# main.net
KiCad netlist of a schematic drawn in Altium Designer
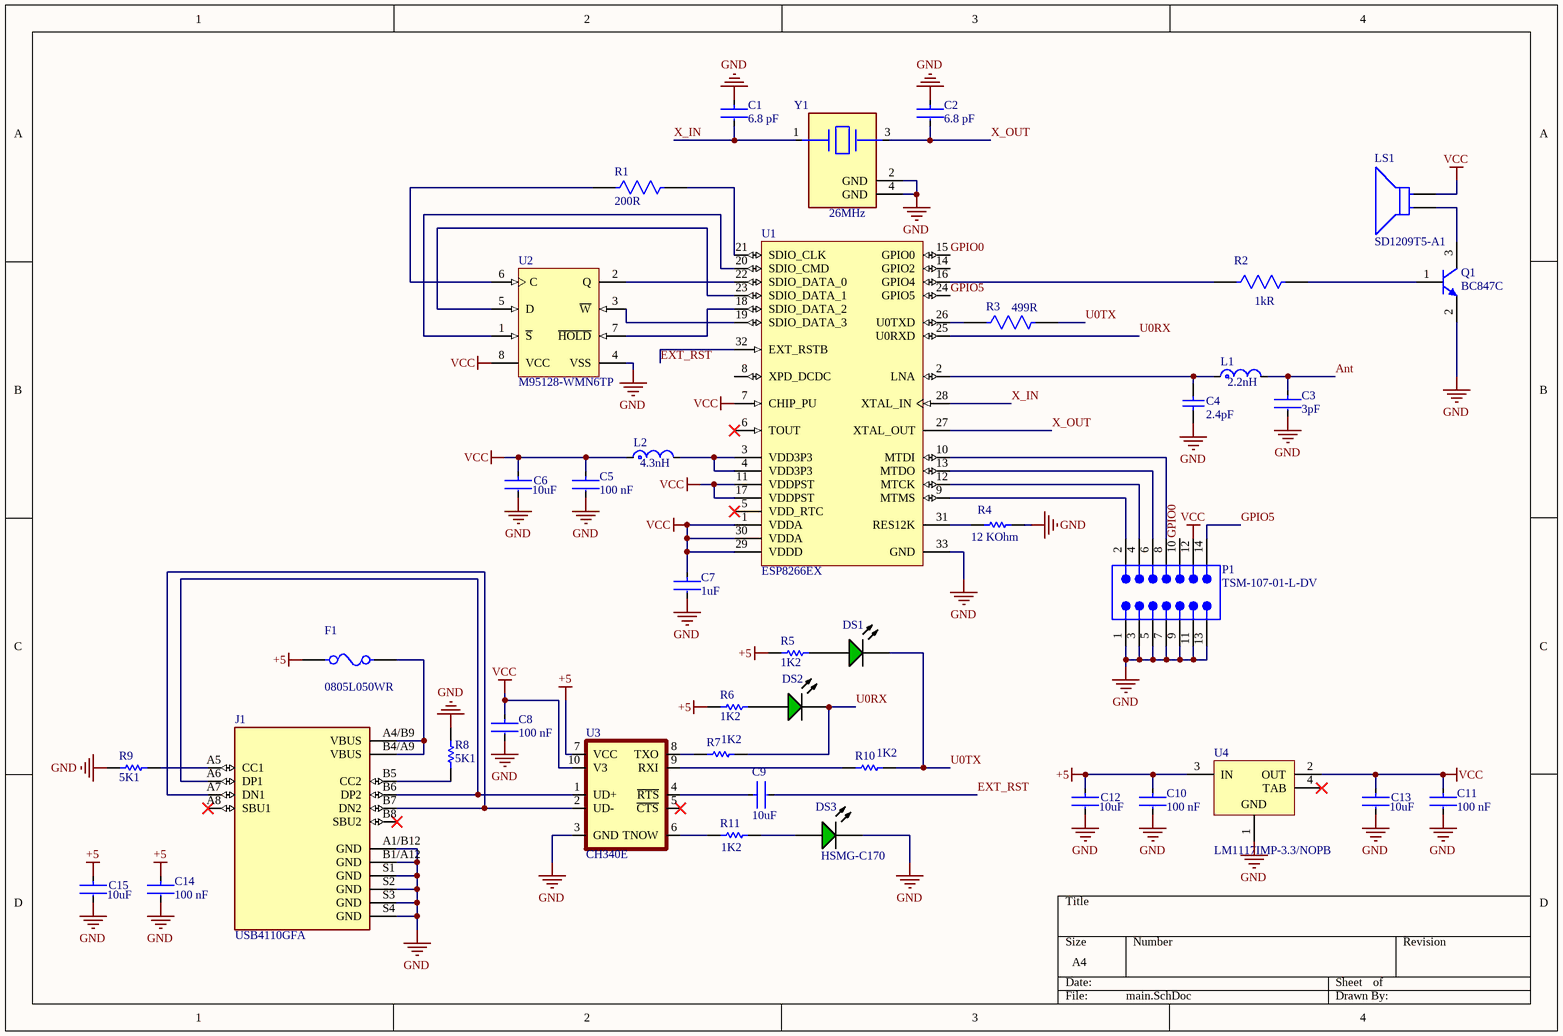
[diagram p0: main.SchDoc]

(export (version "E")
  (design (tool "Eeschema 10.0.6"))
  (components
    (comp (ref "C1")
      (value "C0402C689C5GACTU")
      (footprint "FP-C0402-BB-MFG")
      (description "CAP CER 6.8PF 50V NP0 0402")
      (fields
        (field (name "OCTOPART") "https://octopart.com/c0402c689c5gactu-kemet-9143567")
        (field (name "MANUFACTURER") "Kemet")
        (field (name "CAPACITANCE") "6.8 pF")
      )
      (libsource (lib "Altium Content Vault") (part "b4654b650e69147ec39a6b967a45e02"))
    )
    (comp (ref "C2")
      (value "C0402C689C5GACTU")
      (footprint "FP-C0402-BB-MFG")
      (description "CAP CER 6.8PF 50V NP0 0402")
      (fields
        (field (name "OCTOPART") "https://octopart.com/c0402c689c5gactu-kemet-9143567")
        (field (name "MANUFACTURER") "Kemet")
        (field (name "CAPACITANCE") "6.8 pF")
      )
      (libsource (lib "Altium Content Vault") (part "b4654b650e69147ec39a6b967a45e02"))
    )
    (comp (ref "C3")
      (value "GJM1555C1H3R0BB01D")
      (footprint "FP-GJM155-0_05-IPC_C")
      (description "Multi-Layer Ceramic Capacitor 3pF C0G  ±0.1pF 0402 Paper T/R")
      (fields (field (name "CAPACITANCE") "3pF") (field (name "VOLTAGE") "50V"))
      (libsource (lib "Altium Content Vault") (part "02cd4be3c70576c341d710602a673aa"))
    )
    (comp (ref "C4")
      (value "2.4pF")
      (footprint "CAPC1006X50X20ML10T10")
      (fields
        (field (name "PART NUMBER") "04023J2R4BBSTR")
        (field (name "MANUFACTURER") "AVX Interconnect / Elco")
      )
      (libsource (lib "Altium Content Vault") (part "CAP"))
    )
    (comp (ref "C5")
      (value "100 nF")
      (footprint "FP-CC0402-MFG")
      (description "CAP CER 0.1UF 50V X7R 0402")
      (fields
        (field (name "MANUFACTURER") "YAGEO")
        (field (name "OCTOPART") "https://octopart.com/cc0402krx7r9bb104-yageo-56536067")
      )
      (libsource (lib "Altium Content Vault") (part "11868f565c42a9108669ba33697ecf6"))
    )
    (comp (ref "C6")
      (value "C1608X5R1A106K080AC")
      (footprint "FP-C1608-080-0_1-MFG")
      (description "Multilayer Ceramic Capacitors 10μF ±10% 10V X5R SMD 0603")
      (fields
        (field (name "VOLTAGE") "10V")
        (field (name "TOLERANCE") "10%")
        (field (name "CAPACITANCE") "10uF")
      )
      (libsource (lib "Altium Content Vault") (part "236180d848d6139a670b325ea6854c9"))
    )
    (comp (ref "C7")
      (value "1uF")
      (footprint "FP-GRM15-0_1-MFG")
      (description "CAP CER 1UF 10V X5R 0402")
      (fields
        (field (name "OCTOPART") "https://octopart.com/grm155r61a105ke15d-murata-197442")
        (field (name "MANUFACTURER PART NUMBER") "GRM155R61A105KE15D")
      )
      (libsource (lib "Altium Content Vault") (part "02cd4be3c70576c341d710602a673aa"))
    )
    (comp (ref "C8")
      (value "100 nF")
      (footprint "FP-CC0402-MFG")
      (description "CAP CER 0.1UF 50V X7R 0402")
      (fields
        (field (name "MANUFACTURER") "YAGEO")
        (field (name "OCTOPART") "https://octopart.com/cc0402krx7r9bb104-yageo-56536067")
      )
      (libsource (lib "Altium Content Vault") (part "11868f565c42a9108669ba33697ecf6"))
    )
    (comp (ref "C9")
      (value "C1608X5R1A106K080AC")
      (footprint "FP-C1608-080-0_1-MFG")
      (description "Multilayer Ceramic Capacitors 10μF ±10% 10V X5R SMD 0603")
      (fields
        (field (name "VOLTAGE") "10V")
        (field (name "TOLERANCE") "10%")
        (field (name "CAPACITANCE") "10uF")
      )
      (libsource (lib "Altium Content Vault") (part "236180d848d6139a670b325ea6854c9"))
    )
    (comp (ref "C10")
      (value "100 nF")
      (footprint "FP-CC0402-MFG")
      (description "CAP CER 0.1UF 50V X7R 0402")
      (fields
        (field (name "MANUFACTURER") "YAGEO")
        (field (name "OCTOPART") "https://octopart.com/cc0402krx7r9bb104-yageo-56536067")
      )
      (libsource (lib "Altium Content Vault") (part "11868f565c42a9108669ba33697ecf6"))
    )
    (comp (ref "C11")
      (value "100 nF")
      (footprint "FP-CC0402-MFG")
      (description "CAP CER 0.1UF 50V X7R 0402")
      (fields
        (field (name "MANUFACTURER") "YAGEO")
        (field (name "OCTOPART") "https://octopart.com/cc0402krx7r9bb104-yageo-56536067")
      )
      (libsource (lib "Altium Content Vault") (part "11868f565c42a9108669ba33697ecf6"))
    )
    (comp (ref "C12")
      (value "C1608X5R1A106K080AC")
      (footprint "FP-C1608-080-0_1-MFG")
      (description "Multilayer Ceramic Capacitors 10μF ±10% 10V X5R SMD 0603")
      (fields
        (field (name "VOLTAGE") "10V")
        (field (name "TOLERANCE") "10%")
        (field (name "CAPACITANCE") "10uF")
      )
      (libsource (lib "Altium Content Vault") (part "236180d848d6139a670b325ea6854c9"))
    )
    (comp (ref "C13")
      (value "C1608X5R1A106K080AC")
      (footprint "FP-C1608-080-0_1-MFG")
      (description "Multilayer Ceramic Capacitors 10μF ±10% 10V X5R SMD 0603")
      (fields
        (field (name "VOLTAGE") "10V")
        (field (name "TOLERANCE") "10%")
        (field (name "CAPACITANCE") "10uF")
      )
      (libsource (lib "Altium Content Vault") (part "236180d848d6139a670b325ea6854c9"))
    )
    (comp (ref "C14")
      (value "100 nF")
      (footprint "FP-CC0402-MFG")
      (description "CAP CER 0.1UF 50V X7R 0402")
      (fields
        (field (name "MANUFACTURER") "YAGEO")
        (field (name "OCTOPART") "https://octopart.com/cc0402krx7r9bb104-yageo-56536067")
      )
      (libsource (lib "Altium Content Vault") (part "11868f565c42a9108669ba33697ecf6"))
    )
    (comp (ref "C15")
      (value "C1608X5R1A106K080AC")
      (footprint "FP-C1608-080-0_1-MFG")
      (description "Multilayer Ceramic Capacitors 10μF ±10% 10V X5R SMD 0603")
      (fields
        (field (name "VOLTAGE") "10V")
        (field (name "TOLERANCE") "10%")
        (field (name "CAPACITANCE") "10uF")
      )
      (libsource (lib "Altium Content Vault") (part "236180d848d6139a670b325ea6854c9"))
    )
    (comp (ref "DS1")
      (value "HSMG-C170")
      (footprint "AVAG-HSMX-C170_V")
      (description "Chip LED, Green, 2.2 V, -40 to 85 degC, 2-Pin SMD, Pb-Free, Tape and Reel")
      (fields (field (name "MANUFACTURER") "Avago"))
      (libsource (lib "Altium Content Vault") (part "LED_GREEN_A1K2-2"))
    )
    (comp (ref "DS2")
      (value "HSMG-C170")
      (footprint "AVAG-HSMX-C170_V")
      (description "Chip LED, Green, 2.2 V, -40 to 85 degC, 2-Pin SMD, Pb-Free, Tape and Reel")
      (fields (field (name "MANUFACTURER") "Avago"))
      (libsource (lib "Altium Content Vault") (part "LED_GREEN_A1K2-2"))
    )
    (comp (ref "DS3")
      (value "HSMG-C170")
      (footprint "AVAG-HSMX-C170_V")
      (description "Chip LED, Green, 2.2 V, -40 to 85 degC, 2-Pin SMD, Pb-Free, Tape and Reel")
      (fields (field (name "MANUFACTURER") "Avago"))
      (libsource (lib "Altium Content Vault") (part "LED_GREEN_A1K2-2"))
    )
    (comp (ref "F1")
      (value "0805L050WR")
      (footprint "FP-0805L-MFG")
      (description "PTC RESET FUSE 6V 500MA 0805")
      (fields
        (field (name "MANUFACTURER") "Littelfuse Inc.")
        (field (name "OCTOPART") "https://octopart.com/0805l050wr-littelfuse-673858")
      )
      (libsource (lib "Altium Content Vault") (part "5bcf9b9f640e542cf0359d10258e979"))
    )
    (comp (ref "J1")
      (value "USB4110GFA")
      (footprint "GCT_USB4110GFA")
      (fields (field (name "MF") "Global Connector Technology"))
      (libsource (lib "USB4110GFA") (part "USB4110GFA"))
    )
    (comp (ref "L1")
      (value "LQG15HN2N2S02D")
      (footprint "FP-LQG15HH_02-IPC_C")
      (description "Multilayer type RF Inductor 2.2nH ±0.3nH 0.09Ω 900mA 0402")
      (fields (field (name "INDUCTANCE") "2.2nH"))
      (libsource (lib "Altium Content Vault") (part "4cc4b267dca4c8e51f7102f422741d8"))
    )
    (comp (ref "L2")
      (value "LQG15HN4N3S02D")
      (footprint "FP-LQG15HH_02-MFG")
      (description "Multilayer type RF Inductor 4.3nH ±0.3nH 0.15Ω 700mA 0402")
      (fields (field (name "INDUCTANCE") "4.3nH"))
      (libsource (lib "Altium Content Vault") (part "4cc4b267dca4c8e51f7102f422741d8"))
    )
    (comp (ref "LS1")
      (value "SD1209T5-A1")
      (footprint "FP-SD1209-MFG")
      (description "AUDIO MAGNETIC XDCR 3-6V TH")
      (libsource (lib "Altium Content Vault") (part "1973c4b650225fd2ddacaff6b763965"))
    )
    (comp (ref "P1")
      (value "TSM-107-01-L-DV")
      (footprint "SMTC-TSM-107-01-X-DV")
      (fields (field (name "MANUFACTURER") "Samtec"))
      (libsource (lib "Altium Content Vault") (part "SMTC-TSM-107-01-X-X"))
    )
    (comp (ref "Q1")
      (value "BC847C")
      (footprint "INF-SOT23_L")
      (description "NPN Silicon AF Transistor, 45 V VCEO, 100 mA IC, SOT23, Reel, Green")
      (fields (field (name "MANUFACTURER") "Infineon"))
      (libsource (lib "Altium Content Vault") (part "INF-BJTNPN-BEC-3"))
    )
    (comp (ref "R1")
      (value "CRCW0402200RFKED")
      (footprint "FP-CRCW0402-e3-IPC_C")
      (description "RES Thick Film, 200Ω, 1%, 0.063W, 100ppm/°C, 0402")
      (fields (field (name "RESISTANCE") "200R") (field (name "TOLERANCE") "1%"))
      (libsource (lib "Altium Content Vault") (part "1029c3af85768c4190bb7ad29bc67b5"))
    )
    (comp (ref "R2")
      (value "ERA-3AEB102V")
      (footprint "FP-ERA3A-IPC_C")
      (description "RES SMD 1K OHM 0.1% 1/10W 0603")
      (fields (field (name "TOLERANCE") "0.1%") (field (name "RESISTANCE") "1kR"))
      (libsource (lib "Altium Content Vault") (part "1029c3af85768c4190bb7ad29bc67b5"))
    )
    (comp (ref "R3")
      (value "RC0402FR-07499RL")
      (footprint "FP-RC0402-0_4-IPC_A")
      (description "RES 499 OHM 1% 1/16W 0402")
      (fields (field (name "RESISTANCE") "499R") (field (name "TOLERANCE") "1%"))
      (libsource (lib "Altium Content Vault") (part "1029c3af85768c4190bb7ad29bc67b5"))
    )
    (comp (ref "R4")
      (value "ERJ-2RKF1202X")
      (footprint "RESC1005X40X25ML05T05")
      (description "Chip Resistor, 12 KOhm, +/- 1%, 0.1 W, -55 to 155 degC, 0402 (1005 Metric), RoHS, Tape and Reel")
      (fields (field (name "RESISTANCE") "12 KOhm") (field (name "TOLERANCE") "1%"))
      (libsource (lib "Altium Content Vault") (part "RES-2"))
    )
    (comp (ref "R5")
      (value "1K2")
      (footprint "RESC1005X40X25NL05T05")
      (fields (field (name "PART NUMBER") "CRCW04021K20FKED") (field (name "MANUFACTURER") "Vishay Dale"))
      (libsource (lib "Altium Content Vault") (part "RES"))
    )
    (comp (ref "R6")
      (value "1K2")
      (footprint "RESC1005X40X25NL05T05")
      (fields (field (name "PART NUMBER") "CRCW04021K20FKED") (field (name "MANUFACTURER") "Vishay Dale"))
      (libsource (lib "Altium Content Vault") (part "RES"))
    )
    (comp (ref "R7")
      (value "1K2")
      (footprint "RESC1005X40X25NL05T05")
      (fields (field (name "PART NUMBER") "CRCW04021K20FKED") (field (name "MANUFACTURER") "Vishay Dale"))
      (libsource (lib "Altium Content Vault") (part "RES"))
    )
    (comp (ref "R8")
      (value "5K1")
      (footprint "RESC1608X55X25ML10T15")
      (fields (field (name "MANUFACTURER") "Yageo") (field (name "PART NUMBER") "RC0603FR-075K1L"))
      (libsource (lib "Altium Content Vault") (part "RES"))
    )
    (comp (ref "R9")
      (value "5K1")
      (footprint "RESC1608X55X25ML10T15")
      (fields (field (name "MANUFACTURER") "Yageo") (field (name "PART NUMBER") "RC0603FR-075K1L"))
      (libsource (lib "Altium Content Vault") (part "RES"))
    )
    (comp (ref "R10")
      (value "1K2")
      (footprint "RESC1005X40X25NL05T05")
      (fields (field (name "PART NUMBER") "CRCW04021K20FKED") (field (name "MANUFACTURER") "Vishay Dale"))
      (libsource (lib "Altium Content Vault") (part "RES"))
    )
    (comp (ref "R11")
      (value "1K2")
      (footprint "RESC1005X40X25NL05T05")
      (fields (field (name "PART NUMBER") "CRCW04021K20FKED") (field (name "MANUFACTURER") "Vishay Dale"))
      (libsource (lib "Altium Content Vault") (part "RES"))
    )
    (comp (ref "U1")
      (value "ESP8266EX")
      (footprint "ESFS-QFN-32_L")
      (description "Low-Power, Highly-Integrated Wi-Fi Solution, 2.5 to 3.6 V, 80 mA, -40 to 125 degC, 32-Pin QFN")
      (fields (field (name "MANUFACTURER") "Espressif Systems"))
      (libsource (lib "Altium Content Vault") (part "ESFS-ESP8266EX-32"))
    )
    (comp (ref "U2")
      (value "M95128-WMN6TP")
      (footprint "STM-SO8N-8_V")
      (fields (field (name "MANUFACTURER") "STMicroelectronics"))
      (libsource (lib "Altium Content Vault") (part "STM-M95128-W-SO8N-8"))
    )
    (comp (ref "U3")
      (value "CH340E")
      (footprint "MSOP10")
      (description "USB to serial chip CH340")
      (fields (field (name "MF") "WCH"))
      (libsource (lib "CH340E") (part "CH340E"))
    )
    (comp (ref "U4")
      (value "LM1117IMP-3.3/NOPB")
      (footprint "DCY0004A_N")
      (description "800mA Low-Dropout Linear Regulator, 4-pin SOT-223, Pb-Free")
      (fields (field (name "MANUFACTURER") "Texas Instruments"))
      (libsource (lib "Altium Content Vault") (part "PM-REG-LM1086-SOT4"))
    )
    (comp (ref "Y1")
      (value "ABM11-26.000MHZ-B7G-T")
      (footprint "FP-ABM11-MFG")
      (description "Crystal 26MHz ±15ppm 10pF SMD-4 2mm x 1.6mm")
      (fields (field (name "FREQUENCY") "26MHz") (field (name "TOLERANCE") "15ppm"))
      (libsource (lib "Altium Content Vault") (part "b3c1237d77310e73098bcf11eecb25f"))
    )
  )
  (nets
    (net (code "1") (name "+5") (class "Default")
      (node (ref "C10") (pin "1") (pinfunction "1_1") (pintype "passive"))
      (node (ref "C12") (pin "2") (pinfunction "2_2") (pintype "passive"))
      (node (ref "C14") (pin "1") (pinfunction "1_1") (pintype "passive"))
      (node (ref "C15") (pin "2") (pinfunction "2_2") (pintype "passive"))
      (node (ref "F1") (pin "1") (pinfunction "1_1") (pintype "passive"))
      (node (ref "R5") (pin "2") (pinfunction "2_2") (pintype "passive"))
      (node (ref "R6") (pin "2") (pinfunction "2_2") (pintype "passive"))
      (node (ref "U3") (pin "7") (pinfunction "VCC_7") (pintype "bidirectional"))
      (node (ref "U4") (pin "3") (pinfunction "IN_3") (pintype "power_in"))
    )
    (net (code "2") (name "/Ant") (class "Default")
      (node (ref "C3") (pin "1") (pinfunction "1_1") (pintype "passive"))
      (node (ref "L1") (pin "2") (pinfunction "2_2") (pintype "passive"))
    )
    (net (code "3") (name "/EXT_RST") (class "Default")
      (node (ref "C9") (pin "1") (pinfunction "1_1") (pintype "passive"))
      (node (ref "U1") (pin "32") (pinfunction "EXT_RSTB_32") (pintype "input"))
    )
    (net (code "4") (name "/GPIO0") (class "Default")
      (node (ref "P1") (pin "10") (pinfunction "10_10") (pintype "passive"))
      (node (ref "U1") (pin "15") (pinfunction "GPIO0_15") (pintype "bidirectional"))
    )
    (net (code "5") (name "/GPIO5") (class "Default")
      (node (ref "P1") (pin "14") (pinfunction "14_14") (pintype "passive"))
      (node (ref "U1") (pin "24") (pinfunction "GPIO5_24") (pintype "bidirectional"))
    )
    (net (code "6") (name "/U0RX") (class "Default")
      (node (ref "DS2") (pin "2") (pinfunction "K_2") (pintype "passive"))
      (node (ref "R7") (pin "2") (pinfunction "2_2") (pintype "passive"))
      (node (ref "U1") (pin "25") (pinfunction "U0RXD_25") (pintype "bidirectional"))
    )
    (net (code "7") (name "/U0TX") (class "Default")
      (node (ref "DS1") (pin "2") (pinfunction "K_2") (pintype "passive"))
      (node (ref "R10") (pin "2") (pinfunction "2_2") (pintype "passive"))
      (node (ref "R3") (pin "2") (pinfunction "2_2") (pintype "passive"))
    )
    (net (code "8") (name "/X_IN") (class "Default")
      (node (ref "C1") (pin "2") (pinfunction "2_2") (pintype "passive"))
      (node (ref "U1") (pin "28") (pinfunction "XTAL_IN_28") (pintype "input"))
      (node (ref "Y1") (pin "1") (pinfunction "1_1") (pintype "passive"))
    )
    (net (code "9") (name "/X_OUT") (class "Default")
      (node (ref "C2") (pin "2") (pinfunction "2_2") (pintype "passive"))
      (node (ref "U1") (pin "27") (pinfunction "XTAL_OUT_27") (pintype "passive"))
      (node (ref "Y1") (pin "3") (pinfunction "3_3") (pintype "passive"))
    )
    (net (code "10") (name "GND") (class "Default")
      (node (ref "C1") (pin "1") (pinfunction "1_1") (pintype "passive"))
      (node (ref "C10") (pin "2") (pinfunction "2_2") (pintype "passive"))
      (node (ref "C11") (pin "2") (pinfunction "2_2") (pintype "passive"))
      (node (ref "C12") (pin "1") (pinfunction "1_1") (pintype "passive"))
      (node (ref "C13") (pin "1") (pinfunction "1_1") (pintype "passive"))
      (node (ref "C14") (pin "2") (pinfunction "2_2") (pintype "passive"))
      (node (ref "C15") (pin "1") (pinfunction "1_1") (pintype "passive"))
      (node (ref "C2") (pin "1") (pinfunction "1_1") (pintype "passive"))
      (node (ref "C3") (pin "2") (pinfunction "2_2") (pintype "passive"))
      (node (ref "C4") (pin "2") (pinfunction "2_2") (pintype "passive"))
      (node (ref "C5") (pin "2") (pinfunction "2_2") (pintype "passive"))
      (node (ref "C6") (pin "1") (pinfunction "1_1") (pintype "passive"))
      (node (ref "C7") (pin "2") (pinfunction "2_2") (pintype "passive"))
      (node (ref "C8") (pin "2") (pinfunction "2_2") (pintype "passive"))
      (node (ref "DS3") (pin "2") (pinfunction "K_2") (pintype "passive"))
      (node (ref "J1") (pin "A1/B12") (pinfunction "GND_A1/B12") (pintype "power_in"))
      (node (ref "J1") (pin "B1/A12") (pinfunction "GND_B1/A12") (pintype "power_in"))
      (node (ref "J1") (pin "S1") (pinfunction "GND_S1") (pintype "power_in"))
      (node (ref "J1") (pin "S2") (pinfunction "GND_S2") (pintype "power_in"))
      (node (ref "J1") (pin "S3") (pinfunction "GND_S3") (pintype "power_in"))
      (node (ref "J1") (pin "S4") (pinfunction "GND_S4") (pintype "power_in"))
      (node (ref "P1") (pin "1") (pinfunction "1_1") (pintype "passive"))
      (node (ref "P1") (pin "11") (pinfunction "11_11") (pintype "passive"))
      (node (ref "P1") (pin "13") (pinfunction "13_13") (pintype "passive"))
      (node (ref "P1") (pin "3") (pinfunction "3_3") (pintype "passive"))
      (node (ref "P1") (pin "5") (pinfunction "5_5") (pintype "passive"))
      (node (ref "P1") (pin "7") (pinfunction "7_7") (pintype "passive"))
      (node (ref "P1") (pin "9") (pinfunction "9_9") (pintype "passive"))
      (node (ref "Q1") (pin "2") (pinfunction "E_2") (pintype "passive"))
      (node (ref "R4") (pin "2") (pinfunction "2_2") (pintype "passive"))
      (node (ref "R8") (pin "2") (pinfunction "2_2") (pintype "passive"))
      (node (ref "R9") (pin "1") (pinfunction "1_1") (pintype "passive"))
      (node (ref "U1") (pin "33") (pinfunction "GND_33") (pintype "power_in"))
      (node (ref "U2") (pin "4") (pinfunction "VSS_4") (pintype "power_in"))
      (node (ref "U3") (pin "3") (pinfunction "GND_3") (pintype "bidirectional"))
      (node (ref "U4") (pin "1") (pinfunction "GND_1") (pintype "power_in"))
      (node (ref "Y1") (pin "2") (pinfunction "GND_2") (pintype "power_in"))
      (node (ref "Y1") (pin "4") (pinfunction "GND_4") (pintype "power_in"))
    )
    (net (code "11") (name "Net-(DS1-A)") (class "Default")
      (node (ref "DS1") (pin "1") (pinfunction "A_1") (pintype "passive"))
      (node (ref "R5") (pin "1") (pinfunction "1_1") (pintype "passive"))
    )
    (net (code "12") (name "Net-(DS2-A)") (class "Default")
      (node (ref "DS2") (pin "1") (pinfunction "A_1") (pintype "passive"))
      (node (ref "R6") (pin "1") (pinfunction "1_1") (pintype "passive"))
    )
    (net (code "13") (name "Net-(DS3-A)") (class "Default")
      (node (ref "DS3") (pin "1") (pinfunction "A_1") (pintype "passive"))
      (node (ref "R11") (pin "2") (pinfunction "2_2") (pintype "passive"))
    )
    (net (code "14") (name "Net-(F1-Pad2)") (class "Default")
      (node (ref "F1") (pin "2") (pinfunction "2_2") (pintype "passive"))
      (node (ref "J1") (pin "A4/B9") (pinfunction "VBUS_A4/B9") (pintype "power_in"))
      (node (ref "J1") (pin "B4/A9") (pinfunction "VBUS_B4/A9") (pintype "power_in"))
    )
    (net (code "15") (name "Net-(J1-CC1)") (class "Default")
      (node (ref "J1") (pin "A5") (pinfunction "CC1_A5") (pintype "bidirectional"))
      (node (ref "R9") (pin "2") (pinfunction "2_2") (pintype "passive"))
    )
    (net (code "16") (name "Net-(J1-CC2)") (class "Default")
      (node (ref "J1") (pin "B5") (pinfunction "CC2_B5") (pintype "bidirectional"))
      (node (ref "R8") (pin "1") (pinfunction "1_1") (pintype "passive"))
    )
    (net (code "17") (name "Net-(J1-DN1)") (class "Default")
      (node (ref "J1") (pin "A7") (pinfunction "DN1_A7") (pintype "bidirectional"))
      (node (ref "J1") (pin "B7") (pinfunction "DN2_B7") (pintype "bidirectional"))
      (node (ref "U3") (pin "2") (pinfunction "UD-_2") (pintype "bidirectional"))
    )
    (net (code "18") (name "Net-(J1-DP1)") (class "Default")
      (node (ref "J1") (pin "A6") (pinfunction "DP1_A6") (pintype "bidirectional"))
      (node (ref "J1") (pin "B6") (pinfunction "DP2_B6") (pintype "bidirectional"))
      (node (ref "U3") (pin "1") (pinfunction "UD+_1") (pintype "bidirectional"))
    )
    (net (code "19") (name "Net-(L2-Pad2)") (class "Default")
      (node (ref "L2") (pin "2") (pinfunction "2_2") (pintype "passive"))
      (node (ref "U1") (pin "3") (pinfunction "VDD3P3_3") (pintype "power_in"))
      (node (ref "U1") (pin "4") (pinfunction "VDD3P3_4") (pintype "power_in"))
    )
    (net (code "20") (name "Net-(LS1-C)") (class "Default")
      (node (ref "LS1") (pin "1") (pinfunction "C_1") (pintype "passive"))
      (node (ref "Q1") (pin "3") (pinfunction "C_3") (pintype "passive"))
    )
    (net (code "21") (name "Net-(Q1-B)") (class "Default")
      (node (ref "Q1") (pin "1") (pinfunction "B_1") (pintype "passive"))
      (node (ref "R2") (pin "2") (pinfunction "2_2") (pintype "passive"))
    )
    (net (code "22") (name "Net-(U1-GPIO4)") (class "Default")
      (node (ref "R2") (pin "1") (pinfunction "1_1") (pintype "passive"))
      (node (ref "U1") (pin "16") (pinfunction "GPIO4_16") (pintype "bidirectional"))
    )
    (net (code "23") (name "Net-(U1-LNA)") (class "Default")
      (node (ref "C4") (pin "1") (pinfunction "1_1") (pintype "passive"))
      (node (ref "L1") (pin "1") (pinfunction "1_1") (pintype "passive"))
      (node (ref "U1") (pin "2") (pinfunction "LNA_2") (pintype "bidirectional"))
    )
    (net (code "24") (name "Net-(U1-MTCK)") (class "Default")
      (node (ref "P1") (pin "4") (pinfunction "4_4") (pintype "passive"))
      (node (ref "U1") (pin "12") (pinfunction "MTCK_12") (pintype "bidirectional"))
    )
    (net (code "25") (name "Net-(U1-MTDI)") (class "Default")
      (node (ref "P1") (pin "8") (pinfunction "8_8") (pintype "passive"))
      (node (ref "U1") (pin "10") (pinfunction "MTDI_10") (pintype "bidirectional"))
    )
    (net (code "26") (name "Net-(U1-MTDO)") (class "Default")
      (node (ref "P1") (pin "6") (pinfunction "6_6") (pintype "passive"))
      (node (ref "U1") (pin "13") (pinfunction "MTDO_13") (pintype "bidirectional"))
    )
    (net (code "27") (name "Net-(U1-MTMS)") (class "Default")
      (node (ref "P1") (pin "2") (pinfunction "2_2") (pintype "passive"))
      (node (ref "U1") (pin "9") (pinfunction "MTMS_9") (pintype "bidirectional"))
    )
    (net (code "28") (name "Net-(U1-RES12K)") (class "Default")
      (node (ref "R4") (pin "1") (pinfunction "1_1") (pintype "passive"))
      (node (ref "U1") (pin "31") (pinfunction "RES12K_31") (pintype "passive"))
    )
    (net (code "29") (name "Net-(U1-SDIO_CLK)") (class "Default")
      (node (ref "R1") (pin "2") (pinfunction "2_2") (pintype "passive"))
      (node (ref "U1") (pin "21") (pinfunction "SDIO_CLK_21") (pintype "bidirectional"))
    )
    (net (code "30") (name "Net-(U1-SDIO_CMD)") (class "Default")
      (node (ref "U1") (pin "20") (pinfunction "SDIO_CMD_20") (pintype "bidirectional"))
      (node (ref "U2") (pin "1") (pinfunction "~{S}_1") (pintype "input"))
    )
    (net (code "31") (name "Net-(U1-SDIO_DATA_0)") (class "Default")
      (node (ref "U1") (pin "22") (pinfunction "SDIO_DATA_0_22") (pintype "bidirectional"))
      (node (ref "U2") (pin "2") (pinfunction "Q_2") (pintype "tri_state"))
    )
    (net (code "32") (name "Net-(U1-SDIO_DATA_1)") (class "Default")
      (node (ref "U1") (pin "23") (pinfunction "SDIO_DATA_1_23") (pintype "bidirectional"))
      (node (ref "U2") (pin "5") (pinfunction "D_5") (pintype "input"))
    )
    (net (code "33") (name "Net-(U1-SDIO_DATA_2)") (class "Default")
      (node (ref "U1") (pin "18") (pinfunction "SDIO_DATA_2_18") (pintype "bidirectional"))
      (node (ref "U2") (pin "7") (pinfunction "~{HOLD}_7") (pintype "input"))
    )
    (net (code "34") (name "Net-(U1-SDIO_DATA_3)") (class "Default")
      (node (ref "U1") (pin "19") (pinfunction "SDIO_DATA_3_19") (pintype "bidirectional"))
      (node (ref "U2") (pin "3") (pinfunction "~{W}_3") (pintype "input"))
    )
    (net (code "35") (name "Net-(U1-U0TXD)") (class "Default")
      (node (ref "R3") (pin "1") (pinfunction "1_1") (pintype "passive"))
      (node (ref "U1") (pin "26") (pinfunction "U0TXD_26") (pintype "bidirectional"))
    )
    (net (code "36") (name "Net-(U2-C)") (class "Default")
      (node (ref "R1") (pin "1") (pinfunction "1_1") (pintype "passive"))
      (node (ref "U2") (pin "6") (pinfunction "C_6") (pintype "input"))
    )
    (net (code "37") (name "Net-(U3-RXI)") (class "Default")
      (node (ref "R10") (pin "1") (pinfunction "1_1") (pintype "passive"))
      (node (ref "U3") (pin "9") (pinfunction "RXI_9") (pintype "bidirectional"))
    )
    (net (code "38") (name "Net-(U3-TNOW)") (class "Default")
      (node (ref "R11") (pin "1") (pinfunction "1_1") (pintype "passive"))
      (node (ref "U3") (pin "6") (pinfunction "TNOW_6") (pintype "bidirectional"))
    )
    (net (code "39") (name "Net-(U3-TXO)") (class "Default")
      (node (ref "R7") (pin "1") (pinfunction "1_1") (pintype "passive"))
      (node (ref "U3") (pin "8") (pinfunction "TXO_8") (pintype "bidirectional"))
    )
    (net (code "40") (name "Net-(U3-~{RTS})") (class "Default")
      (node (ref "C9") (pin "2") (pinfunction "2_2") (pintype "passive"))
      (node (ref "U3") (pin "4") (pinfunction "~{RTS}_4") (pintype "bidirectional"))
    )
    (net (code "41") (name "VCC") (class "Default")
      (node (ref "C11") (pin "1") (pinfunction "1_1") (pintype "passive"))
      (node (ref "C13") (pin "2") (pinfunction "2_2") (pintype "passive"))
      (node (ref "C5") (pin "1") (pinfunction "1_1") (pintype "passive"))
      (node (ref "C6") (pin "2") (pinfunction "2_2") (pintype "passive"))
      (node (ref "C7") (pin "1") (pinfunction "1_1") (pintype "passive"))
      (node (ref "C8") (pin "1") (pinfunction "1_1") (pintype "passive"))
      (node (ref "L2") (pin "1") (pinfunction "1_1") (pintype "passive"))
      (node (ref "LS1") (pin "2") (pinfunction "A_2") (pintype "passive"))
      (node (ref "P1") (pin "12") (pinfunction "12_12") (pintype "passive"))
      (node (ref "U1") (pin "1") (pinfunction "VDDA_1") (pintype "power_in"))
      (node (ref "U1") (pin "11") (pinfunction "VDDPST_11") (pintype "power_in"))
      (node (ref "U1") (pin "17") (pinfunction "VDDPST_17") (pintype "power_in"))
      (node (ref "U1") (pin "29") (pinfunction "VDDD_29") (pintype "power_in"))
      (node (ref "U1") (pin "30") (pinfunction "VDDA_30") (pintype "power_in"))
      (node (ref "U1") (pin "7") (pinfunction "CHIP_PU_7") (pintype "input"))
      (node (ref "U2") (pin "8") (pinfunction "VCC_8") (pintype "power_in"))
      (node (ref "U3") (pin "10") (pinfunction "V3_10") (pintype "bidirectional"))
      (node (ref "U4") (pin "2") (pinfunction "OUT_2") (pintype "power_in"))
    )
    (net (code "42") (name "unconnected-(J1-SBU1-PadA8)") (class "Default")
      (node (ref "J1") (pin "A8") (pinfunction "SBU1_A8") (pintype "bidirectional+no_connect"))
    )
    (net (code "43") (name "unconnected-(J1-SBU2-PadB8)") (class "Default")
      (node (ref "J1") (pin "B8") (pinfunction "SBU2_B8") (pintype "bidirectional+no_connect"))
    )
    (net (code "44") (name "unconnected-(U1-GPIO2-Pad14)") (class "Default")
      (node (ref "U1") (pin "14") (pinfunction "GPIO2_14") (pintype "bidirectional"))
    )
    (net (code "45") (name "unconnected-(U1-TOUT-Pad6)") (class "Default")
      (node (ref "U1") (pin "6") (pinfunction "TOUT_6") (pintype "input+no_connect"))
    )
    (net (code "46") (name "unconnected-(U1-VDD_RTC-Pad5)") (class "Default")
      (node (ref "U1") (pin "5") (pinfunction "VDD_RTC_5") (pintype "power_in+no_connect"))
    )
    (net (code "47") (name "unconnected-(U1-XPD_DCDC-Pad8)") (class "Default")
      (node (ref "U1") (pin "8") (pinfunction "XPD_DCDC_8") (pintype "bidirectional"))
    )
    (net (code "48") (name "unconnected-(U3-~{CTS}-Pad5)") (class "Default")
      (node (ref "U3") (pin "5") (pinfunction "~{CTS}_5") (pintype "bidirectional+no_connect"))
    )
    (net (code "49") (name "unconnected-(U4-TAB-Pad4)") (class "Default")
      (node (ref "U4") (pin "4") (pinfunction "TAB_4") (pintype "power_in+no_connect"))
    )
  )
)
